# Schematic.net
KiCad netlist of a schematic drawn in Altium Designer
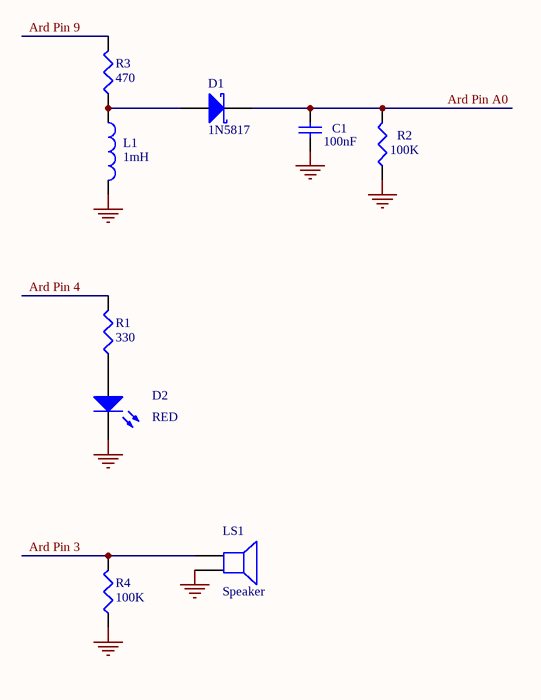
[diagram p0: Schematic.SchDoc]

(export (version "E")
  (design (tool "Eeschema 10.0.6"))
  (components
    (comp (ref "C1")
      (value "100nF")
      (description "Capacitor")
      (libsource (lib "Miscellaneous Devices") (part "Cap"))
    )
    (comp (ref "D1")
      (value "1N5817")
      (description "Schottky Diode")
      (libsource (lib "Miscellaneous Devices") (part "D Schottky"))
    )
    (comp (ref "D2")
      (value "RED")
      (description "Red LED")
      (libsource (lib "Miscellaneous Devices") (part "LED0"))
    )
    (comp (ref "L1")
      (value "1mH")
      (description "Inductor")
      (libsource (lib "Miscellaneous Devices") (part "Inductor"))
    )
    (comp (ref "LS1")
      (value "Speaker")
      (description "Piezo speaker")
      (libsource (lib "Miscellaneous Devices") (part "Speaker"))
    )
    (comp (ref "R1")
      (value "330")
      (description "Resistor")
      (libsource (lib "Miscellaneous Devices") (part "Res3"))
    )
    (comp (ref "R2")
      (value "100K")
      (description "Resistor")
      (libsource (lib "Miscellaneous Devices") (part "Res3"))
    )
    (comp (ref "R3")
      (value "470")
      (description "Resistor")
      (libsource (lib "Miscellaneous Devices") (part "Res3"))
    )
    (comp (ref "R4")
      (value "100K")
      (description "Resistor")
      (libsource (lib "Miscellaneous Devices") (part "Res3"))
    )
  )
  (nets
    (net (code "1") (name "/Ard Pin 3") (class "Default")
      (node (ref "LS1") (pin "1") (pinfunction "1_1") (pintype "passive"))
      (node (ref "R4") (pin "2") (pinfunction "2_2") (pintype "passive"))
    )
    (net (code "2") (name "/Ard Pin 4") (class "Default")
      (node (ref "R1") (pin "2") (pinfunction "2_2") (pintype "passive"))
    )
    (net (code "3") (name "/Ard Pin 9") (class "Default")
      (node (ref "R3") (pin "2") (pinfunction "2_2") (pintype "passive"))
    )
    (net (code "4") (name "/Ard Pin A0") (class "Default")
      (node (ref "C1") (pin "2") (pinfunction "2_2") (pintype "passive"))
      (node (ref "D1") (pin "2") (pinfunction "K_2") (pintype "passive"))
      (node (ref "R2") (pin "2") (pinfunction "2_2") (pintype "passive"))
    )
    (net (code "5") (name "GND") (class "Default")
      (node (ref "C1") (pin "1") (pinfunction "1_1") (pintype "passive"))
      (node (ref "D2") (pin "2") (pinfunction "K_2") (pintype "passive"))
      (node (ref "L1") (pin "2") (pinfunction "2_2") (pintype "passive"))
      (node (ref "LS1") (pin "2") (pinfunction "2_2") (pintype "passive"))
      (node (ref "R2") (pin "1") (pinfunction "1_1") (pintype "passive"))
      (node (ref "R4") (pin "1") (pinfunction "1_1") (pintype "passive"))
    )
    (net (code "6") (name "Net-(D1-A)") (class "Default")
      (node (ref "D1") (pin "1") (pinfunction "A_1") (pintype "passive"))
      (node (ref "L1") (pin "1") (pinfunction "1_1") (pintype "passive"))
      (node (ref "R3") (pin "1") (pinfunction "1_1") (pintype "passive"))
    )
    (net (code "7") (name "Net-(D2-A)") (class "Default")
      (node (ref "D2") (pin "1") (pinfunction "A_1") (pintype "passive"))
      (node (ref "R1") (pin "1") (pinfunction "1_1") (pintype "passive"))
    )
  )
)
